# Robonaut.net
KiCad netlist of a schematic drawn in Altium Designer
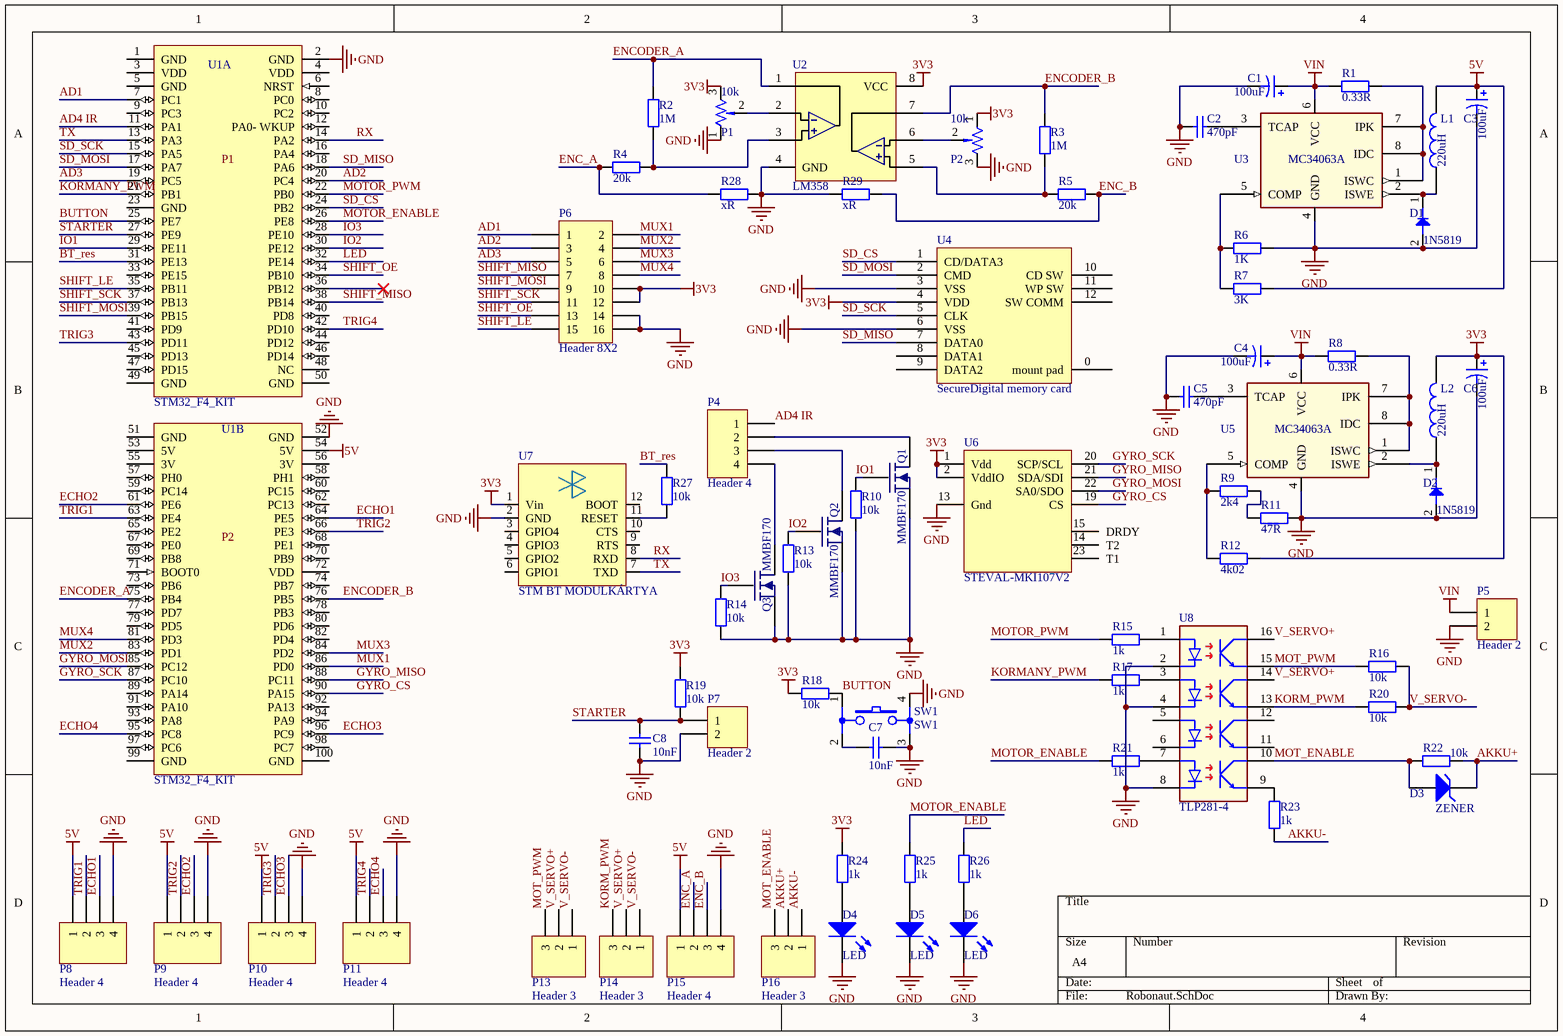
[diagram p0: Robonaut.SchDoc]

(export (version "E")
  (design (tool "Eeschema 10.0.6"))
  (components
    (comp (ref "C1")
      (value "100uF")
      (footprint "FP_CAP_ELKO_6,3X6,3")
      (description "Polarized Capacitor")
      (libsource (lib "Capacitor") (part "CAP_ELECT"))
    )
    (comp (ref "C2")
      (value "470pF")
      (footprint "FP_0805_CAP_085")
      (description "Capacitor")
      (libsource (lib "Capacitor") (part "CAP"))
    )
    (comp (ref "C3")
      (value "100uF")
      (footprint "FP_CAP_ELKO_6,3X6,3")
      (description "Polarized Capacitor")
      (libsource (lib "Capacitor") (part "CAP_ELECT"))
    )
    (comp (ref "C4")
      (value "100uF")
      (footprint "FP_CAP_ELKO_6,3X6,3")
      (description "Polarized Capacitor")
      (libsource (lib "Capacitor") (part "CAP_ELECT"))
    )
    (comp (ref "C5")
      (value "470pF")
      (footprint "FP_0805_CAP_085")
      (description "Capacitor")
      (libsource (lib "Capacitor") (part "CAP"))
    )
    (comp (ref "C6")
      (value "100uF")
      (footprint "FP_CAP_ELKO_6,3X6,3")
      (description "Polarized Capacitor")
      (libsource (lib "Capacitor") (part "CAP_ELECT"))
    )
    (comp (ref "C7")
      (value "10nF")
      (footprint "FP_0805_CAP_085")
      (description "Capacitor")
      (libsource (lib "Capacitor") (part "CAP"))
    )
    (comp (ref "C8")
      (value "10nF")
      (footprint "FP_0805_CAP_085")
      (description "Capacitor")
      (libsource (lib "Capacitor") (part "CAP"))
    )
    (comp (ref "D1") (value "1N5819") (footprint "FP_SOD-123") (libsource (lib "Diode") (part "DIODE")))
    (comp (ref "D2") (value "1N5819") (footprint "FP_SOD-123") (libsource (lib "Diode") (part "DIODE")))
    (comp (ref "D3")
      (value "ZENER")
      (footprint "FP_SOD-123")
      (description "Zener Diode")
      (libsource (lib "Diode") (part "ZENER"))
    )
    (comp (ref "D4")
      (value "LED")
      (footprint "FP_0805_LED_RED")
      (description "Typical RED GaAs LED")
      (libsource (lib "Led_optical") (part "LED"))
    )
    (comp (ref "D5")
      (value "LED")
      (footprint "FP_0805_LED_RED")
      (description "Typical RED GaAs LED")
      (libsource (lib "Led_optical") (part "LED"))
    )
    (comp (ref "D6")
      (value "LED")
      (footprint "FP_0805_LED_RED")
      (description "Typical RED GaAs LED")
      (libsource (lib "Led_optical") (part "LED"))
    )
    (comp (ref "L1")
      (value "220uH")
      (footprint "FP_IND_MURATA3131")
      (description "Inductor")
      (libsource (lib "Inductor") (part "IND"))
    )
    (comp (ref "L2")
      (value "220uH")
      (footprint "FP_IND_MURATA3131")
      (description "Inductor")
      (libsource (lib "Inductor") (part "IND"))
    )
    (comp (ref "P1") (value "10k") (footprint "Res Trimmer TH") (libsource (lib "Resistor") (part "POTI")))
    (comp (ref "P2") (value "10k") (footprint "Res Trimmer TH") (libsource (lib "Resistor") (part "POTI")))
    (comp (ref "P4")
      (value "Header 4")
      (footprint "HDR1X4")
      (description "Header, 4-Pin")
      (fields (field (name "PUBLISHER") "Altium Limited"))
      (libsource (lib "") (part "Header 4_1"))
    )
    (comp (ref "P5")
      (value "Header 2")
      (footprint "HDR1X2")
      (description "Header, 2-Pin")
      (fields (field (name "PUBLISHER") "Altium Limited"))
      (libsource (lib "Miscellaneous Connectors") (part "Header 2"))
    )
    (comp (ref "P6")
      (value "Header 8X2")
      (footprint "HDR2X8")
      (description "Header, 8-Pin, Dual row")
      (fields (field (name "PUBLISHER") "Altium Limited"))
      (libsource (lib "Miscellaneous Connectors") (part "Header 8X2"))
    )
    (comp (ref "P7")
      (value "Header 2")
      (footprint "HDR1X2")
      (description "Header, 2-Pin")
      (fields (field (name "PUBLISHER") "Altium Limited"))
      (libsource (lib "Miscellaneous Connectors") (part "Header 2"))
    )
    (comp (ref "P8")
      (value "Header 4")
      (footprint "HDR1X4")
      (description "Header, 4-Pin")
      (fields (field (name "PUBLISHER") "Altium Limited"))
      (libsource (lib "Miscellaneous Connectors") (part "Header 4"))
    )
    (comp (ref "P9")
      (value "Header 4")
      (footprint "HDR1X4")
      (description "Header, 4-Pin")
      (fields (field (name "PUBLISHER") "Altium Limited"))
      (libsource (lib "Miscellaneous Connectors") (part "Header 4"))
    )
    (comp (ref "P10")
      (value "Header 4")
      (footprint "HDR1X4")
      (description "Header, 4-Pin")
      (fields (field (name "PUBLISHER") "Altium Limited"))
      (libsource (lib "Miscellaneous Connectors") (part "Header 4"))
    )
    (comp (ref "P11")
      (value "Header 4")
      (footprint "HDR1X4")
      (description "Header, 4-Pin")
      (fields (field (name "PUBLISHER") "Altium Limited"))
      (libsource (lib "Miscellaneous Connectors") (part "Header 4"))
    )
    (comp (ref "P13")
      (value "Header 3")
      (footprint "HDR1X3")
      (description "Header, 3-Pin")
      (fields (field (name "PUBLISHER") "Altium Limited"))
      (libsource (lib "Miscellaneous Connectors") (part "Header 3"))
    )
    (comp (ref "P14")
      (value "Header 3")
      (footprint "HDR1X3")
      (description "Header, 3-Pin")
      (fields (field (name "PUBLISHER") "Altium Limited"))
      (libsource (lib "Miscellaneous Connectors") (part "Header 3"))
    )
    (comp (ref "P15")
      (value "Header 4")
      (footprint "HDR1X4")
      (description "Header, 4-Pin")
      (fields (field (name "PUBLISHER") "Altium Limited"))
      (libsource (lib "Miscellaneous Connectors") (part "Header 4"))
    )
    (comp (ref "P16")
      (value "Header 3")
      (footprint "HDR1X3")
      (description "Header, 3-Pin")
      (fields (field (name "PUBLISHER") "Altium Limited"))
      (libsource (lib "Miscellaneous Connectors") (part "Header 3"))
    )
    (comp (ref "Q1")
      (value "MMBF170")
      (footprint "BBMF170")
      (description "N fet  60V 500mA")
      (libsource (lib "FET") (part "MMBF170"))
    )
    (comp (ref "Q2")
      (value "MMBF170")
      (footprint "BBMF170")
      (description "N fet  60V 500mA")
      (libsource (lib "FET") (part "MMBF170"))
    )
    (comp (ref "Q3")
      (value "MMBF170")
      (footprint "BBMF170")
      (description "N fet  60V 500mA")
      (libsource (lib "FET") (part "MMBF170"))
    )
    (comp (ref "R1")
      (value "0.33R")
      (footprint "FP_0805_RES")
      (description "Resistor")
      (libsource (lib "Resistor") (part "RES"))
    )
    (comp (ref "R2")
      (value "1M")
      (footprint "FP_0805_RES")
      (description "Resistor")
      (libsource (lib "") (part "RES_1"))
    )
    (comp (ref "R3")
      (value "1M")
      (footprint "FP_0805_RES")
      (description "Resistor")
      (libsource (lib "") (part "RES_1"))
    )
    (comp (ref "R4")
      (value "20k")
      (footprint "FP_0805_RES")
      (description "Resistor")
      (libsource (lib "Resistor") (part "RES"))
    )
    (comp (ref "R5")
      (value "20k")
      (footprint "FP_0805_RES")
      (description "Resistor")
      (libsource (lib "Resistor") (part "RES"))
    )
    (comp (ref "R6")
      (value "1K")
      (footprint "FP_0805_RES")
      (description "Resistor")
      (libsource (lib "Resistor") (part "RES"))
    )
    (comp (ref "R7")
      (value "3K")
      (footprint "FP_0805_RES")
      (description "Resistor")
      (libsource (lib "Resistor") (part "RES"))
    )
    (comp (ref "R8")
      (value "0.33R")
      (footprint "FP_0805_RES")
      (description "Resistor")
      (libsource (lib "Resistor") (part "RES"))
    )
    (comp (ref "R9")
      (value "2k4")
      (footprint "FP_0805_RES")
      (description "Resistor")
      (libsource (lib "Resistor") (part "RES"))
    )
    (comp (ref "R10")
      (value "10k")
      (footprint "FP_0805_RES")
      (description "Resistor")
      (libsource (lib "") (part "RES_1"))
    )
    (comp (ref "R11")
      (value "47R")
      (footprint "FP_0805_RES")
      (description "Resistor")
      (libsource (lib "Resistor") (part "RES"))
    )
    (comp (ref "R12")
      (value "4k02")
      (footprint "FP_0805_RES")
      (description "Resistor")
      (libsource (lib "Resistor") (part "RES"))
    )
    (comp (ref "R13")
      (value "10k")
      (footprint "FP_0805_RES")
      (description "Resistor")
      (libsource (lib "") (part "RES_1"))
    )
    (comp (ref "R14")
      (value "10k")
      (footprint "FP_0805_RES")
      (description "Resistor")
      (libsource (lib "") (part "RES_1"))
    )
    (comp (ref "R15")
      (value "1k")
      (footprint "FP_0805_RES")
      (description "Resistor")
      (libsource (lib "Resistor") (part "RES"))
    )
    (comp (ref "R16")
      (value "10k")
      (footprint "FP_0805_RES")
      (description "Resistor")
      (libsource (lib "Resistor") (part "RES"))
    )
    (comp (ref "R17")
      (value "1k")
      (footprint "FP_0805_RES")
      (description "Resistor")
      (libsource (lib "Resistor") (part "RES"))
    )
    (comp (ref "R18")
      (value "10k")
      (footprint "FP_0805_RES")
      (description "Resistor")
      (libsource (lib "Resistor") (part "RES"))
    )
    (comp (ref "R19")
      (value "10k")
      (footprint "FP_0805_RES")
      (description "Resistor")
      (libsource (lib "") (part "RES_1"))
    )
    (comp (ref "R20")
      (value "10k")
      (footprint "FP_0805_RES")
      (description "Resistor")
      (libsource (lib "Resistor") (part "RES"))
    )
    (comp (ref "R21")
      (value "1k")
      (footprint "FP_0805_RES")
      (description "Resistor")
      (libsource (lib "Resistor") (part "RES"))
    )
    (comp (ref "R22")
      (value "10k")
      (footprint "FP_0805_RES")
      (description "Resistor")
      (libsource (lib "Resistor") (part "RES"))
    )
    (comp (ref "R23")
      (value "1k")
      (footprint "FP_0805_RES")
      (description "Resistor")
      (libsource (lib "") (part "RES_1"))
    )
    (comp (ref "R24")
      (value "1k")
      (footprint "FP_0805_RES")
      (description "Resistor")
      (libsource (lib "") (part "RES_1"))
    )
    (comp (ref "R25")
      (value "1k")
      (footprint "FP_0805_RES")
      (description "Resistor")
      (libsource (lib "") (part "RES_1"))
    )
    (comp (ref "R26")
      (value "1k")
      (footprint "FP_0805_RES")
      (description "Resistor")
      (libsource (lib "") (part "RES_1"))
    )
    (comp (ref "R27")
      (value "10k")
      (footprint "FP_0805_RES")
      (description "Resistor")
      (libsource (lib "") (part "RES_1"))
    )
    (comp (ref "R28")
      (value "xR")
      (footprint "FP_0805_RES")
      (description "Resistor")
      (libsource (lib "Resistor") (part "RES"))
    )
    (comp (ref "R29")
      (value "xR")
      (footprint "FP_0805_RES")
      (description "Resistor")
      (libsource (lib "Resistor") (part "RES"))
    )
    (comp (ref "SW1") (value "SW1") (footprint "FP_TACTBTN") (libsource (lib "Switch") (part "SW1")))
    (comp (ref "U1")
      (value "STM32_F4_KIT")
      (footprint "FP_STM32F4DISC")
      (description "STM32 F4 Discovery Evaluation Kit")
      (libsource (lib "Modul") (part "STM32F4DISCOVERY"))
    )
    (comp (ref "U2")
      (value "LM358")
      (footprint "FP_SO8_MS012AA")
      (description "Low power dual operational amplifiers")
      (libsource (lib "Analog") (part "LM358"))
    )
    (comp (ref "U3")
      (value "MC34063A")
      (footprint "FP_SO8_MS012AA")
      (libsource (lib "Supply") (part "MC34063A"))
    )
    (comp (ref "U4")
      (value "SecureDigital memory card")
      (footprint "FP_CONN_SD")
      (libsource (lib "Connector") (part "SD card"))
    )
    (comp (ref "U5")
      (value "MC34063A")
      (footprint "FP_SO8_MS012AA")
      (libsource (lib "Supply") (part "MC34063A"))
    )
    (comp (ref "U6")
      (value "STEVAL-MKI107V2")
      (footprint "STEVAL-MKI107V2 DIL24 Adapter")
      (description "Three-axis digital output gyroscope")
      (fields (field (name "MANUFACTURER") "STMicroelectronic"))
      (libsource (lib "Modul") (part "STEVAL-MKI107V2"))
    )
    (comp (ref "U7")
      (value "STM BT MODULKÁRTYA")
      (footprint "STM BT MODUL")
      (description "bluetooth modulkártya")
      (libsource (lib "Modul") (part "STM BT MODULKÁRTYA"))
    )
    (comp (ref "U8")
      (value "TLP281-4")
      (footprint "TLP281-4")
      (description "Optocsatoló 4X")
      (libsource (lib "Led_optical") (part "TLP281-4"))
    )
  )
  (nets
    (net (code "1") (name "/AD1") (class "Default")
      (node (ref "P6") (pin "1") (pinfunction "1_1") (pintype "passive"))
      (node (ref "U1") (pin "7") (pinfunction "PC1_7") (pintype "bidirectional"))
    )
    (net (code "2") (name "/AD2") (class "Default")
      (node (ref "P6") (pin "3") (pinfunction "3_3") (pintype "passive"))
      (node (ref "U1") (pin "20") (pinfunction "PC4_20") (pintype "bidirectional"))
    )
    (net (code "3") (name "/AD3") (class "Default")
      (node (ref "P6") (pin "5") (pinfunction "5_5") (pintype "passive"))
      (node (ref "U1") (pin "19") (pinfunction "PC5_19") (pintype "bidirectional"))
    )
    (net (code "4") (name "/AD4 IR") (class "Default")
      (node (ref "P4") (pin "1") (pinfunction "1_1") (pintype "passive"))
      (node (ref "U1") (pin "11") (pinfunction "PA1_11") (pintype "bidirectional"))
    )
    (net (code "5") (name "/AKKU+") (class "Default")
      (node (ref "D3") (pin "2") (pinfunction "K_2") (pintype "passive"))
      (node (ref "P16") (pin "2") (pinfunction "2_2") (pintype "passive"))
      (node (ref "R22") (pin "2") (pinfunction "2_2") (pintype "passive"))
    )
    (net (code "6") (name "/AKKU-") (class "Default")
      (node (ref "P16") (pin "1") (pinfunction "1_1") (pintype "passive"))
      (node (ref "R23") (pin "1") (pinfunction "1_1") (pintype "passive"))
    )
    (net (code "7") (name "/BT_res") (class "Default")
      (node (ref "R27") (pin "2") (pinfunction "2_2") (pintype "passive"))
      (node (ref "U1") (pin "31") (pinfunction "PE13_31") (pintype "bidirectional"))
    )
    (net (code "8") (name "/BUTTON") (class "Default")
      (node (ref "R18") (pin "2") (pinfunction "2_2") (pintype "passive"))
      (node (ref "SW1") (pin "1") (pinfunction "1_1") (pintype "passive"))
      (node (ref "U1") (pin "25") (pinfunction "PE7_25") (pintype "bidirectional"))
    )
    (net (code "9") (name "/ECHO1") (class "Default")
      (node (ref "P8") (pin "3") (pinfunction "3_3") (pintype "passive"))
      (node (ref "U1") (pin "64") (pinfunction "PE5_64") (pintype "bidirectional"))
    )
    (net (code "10") (name "/ECHO2") (class "Default")
      (node (ref "P9") (pin "3") (pinfunction "3_3") (pintype "passive"))
      (node (ref "U1") (pin "61") (pinfunction "PE6_61") (pintype "bidirectional"))
    )
    (net (code "11") (name "/ECHO3") (class "Default")
      (node (ref "P10") (pin "3") (pinfunction "3_3") (pintype "passive"))
      (node (ref "U1") (pin "96") (pinfunction "PC9_96") (pintype "bidirectional"))
    )
    (net (code "12") (name "/ECHO4") (class "Default")
      (node (ref "P11") (pin "3") (pinfunction "3_3") (pintype "passive"))
      (node (ref "U1") (pin "95") (pinfunction "PC8_95") (pintype "bidirectional"))
    )
    (net (code "13") (name "/ENCODER_A") (class "Default")
      (node (ref "R2") (pin "2") (pinfunction "2_2") (pintype "passive"))
      (node (ref "U1") (pin "75") (pinfunction "PB4_75") (pintype "bidirectional"))
      (node (ref "U2") (pin "1") (pintype "passive"))
    )
    (net (code "14") (name "/ENCODER_B") (class "Default")
      (node (ref "R3") (pin "2") (pinfunction "2_2") (pintype "passive"))
      (node (ref "U1") (pin "76") (pinfunction "PB5_76") (pintype "bidirectional"))
      (node (ref "U2") (pin "7") (pintype "passive"))
    )
    (net (code "15") (name "/ENC_A") (class "Default")
      (node (ref "P15") (pin "2") (pinfunction "2_2") (pintype "passive"))
      (node (ref "R28") (pin "1") (pinfunction "1_1") (pintype "passive"))
      (node (ref "R4") (pin "1") (pinfunction "1_1") (pintype "passive"))
    )
    (net (code "16") (name "/ENC_B") (class "Default")
      (node (ref "P15") (pin "3") (pinfunction "3_3") (pintype "passive"))
      (node (ref "R29") (pin "2") (pinfunction "2_2") (pintype "passive"))
      (node (ref "R5") (pin "2") (pinfunction "2_2") (pintype "passive"))
    )
    (net (code "17") (name "/GYRO_CS") (class "Default")
      (node (ref "U1") (pin "90") (pinfunction "PA15_90") (pintype "bidirectional"))
      (node (ref "U6") (pin "19") (pinfunction "CS_19") (pintype "passive"))
    )
    (net (code "18") (name "/GYRO_MISO") (class "Default")
      (node (ref "U1") (pin "88") (pinfunction "PC11_88") (pintype "bidirectional"))
      (node (ref "U6") (pin "21") (pinfunction "SDA/SDI_21") (pintype "passive"))
    )
    (net (code "19") (name "/GYRO_MOSI") (class "Default")
      (node (ref "U1") (pin "85") (pinfunction "PC12_85") (pintype "bidirectional"))
      (node (ref "U6") (pin "22") (pinfunction "SA0/SDO_22") (pintype "passive"))
    )
    (net (code "20") (name "/GYRO_SCK") (class "Default")
      (node (ref "U1") (pin "87") (pinfunction "PC10_87") (pintype "bidirectional"))
      (node (ref "U6") (pin "20") (pinfunction "SCP/SCL_20") (pintype "passive"))
    )
    (net (code "21") (name "/IO1") (class "Default")
      (node (ref "Q1") (pin "G") (pinfunction "G_G") (pintype "passive"))
      (node (ref "R10") (pin "2") (pinfunction "2_2") (pintype "passive"))
      (node (ref "U1") (pin "29") (pinfunction "PE11_29") (pintype "bidirectional"))
    )
    (net (code "22") (name "/IO2") (class "Default")
      (node (ref "Q2") (pin "G") (pinfunction "G_G") (pintype "passive"))
      (node (ref "R13") (pin "2") (pinfunction "2_2") (pintype "passive"))
      (node (ref "U1") (pin "30") (pinfunction "PE12_30") (pintype "bidirectional"))
    )
    (net (code "23") (name "/IO3") (class "Default")
      (node (ref "Q3") (pin "G") (pinfunction "G_G") (pintype "passive"))
      (node (ref "R14") (pin "2") (pinfunction "2_2") (pintype "passive"))
      (node (ref "U1") (pin "28") (pinfunction "PE10_28") (pintype "bidirectional"))
    )
    (net (code "24") (name "/KORMANY_PWM") (class "Default")
      (node (ref "R17") (pin "1") (pinfunction "1_1") (pintype "passive"))
      (node (ref "U1") (pin "21") (pinfunction "PB1_21") (pintype "bidirectional"))
    )
    (net (code "25") (name "/KORM_PWM") (class "Default")
      (node (ref "P14") (pin "3") (pinfunction "3_3") (pintype "passive"))
      (node (ref "R20") (pin "1") (pinfunction "1_1") (pintype "passive"))
      (node (ref "U8") (pin "13") (pintype "passive"))
    )
    (net (code "26") (name "/LED") (class "Default")
      (node (ref "R26") (pin "2") (pinfunction "2_2") (pintype "passive"))
      (node (ref "U1") (pin "32") (pinfunction "PE14_32") (pintype "bidirectional"))
    )
    (net (code "27") (name "/MOTOR_ENABLE") (class "Default")
      (node (ref "R21") (pin "1") (pinfunction "1_1") (pintype "passive"))
      (node (ref "R25") (pin "2") (pinfunction "2_2") (pintype "passive"))
      (node (ref "U1") (pin "26") (pinfunction "PE8_26") (pintype "bidirectional"))
    )
    (net (code "28") (name "/MOTOR_PWM") (class "Default")
      (node (ref "R15") (pin "1") (pinfunction "1_1") (pintype "passive"))
      (node (ref "U1") (pin "22") (pinfunction "PB0_22") (pintype "bidirectional"))
    )
    (net (code "29") (name "/MOT_ENABLE") (class "Default")
      (node (ref "D3") (pin "1") (pinfunction "A_1") (pintype "passive"))
      (node (ref "P16") (pin "3") (pinfunction "3_3") (pintype "passive"))
      (node (ref "R22") (pin "1") (pinfunction "1_1") (pintype "passive"))
      (node (ref "U8") (pin "10") (pintype "passive"))
    )
    (net (code "30") (name "/MOT_PWM") (class "Default")
      (node (ref "P13") (pin "3") (pinfunction "3_3") (pintype "passive"))
      (node (ref "R16") (pin "1") (pinfunction "1_1") (pintype "passive"))
      (node (ref "U8") (pin "15") (pintype "passive"))
    )
    (net (code "31") (name "/MUX1") (class "Default")
      (node (ref "P6") (pin "2") (pinfunction "2_2") (pintype "passive"))
      (node (ref "U1") (pin "86") (pinfunction "PD0_86") (pintype "bidirectional"))
    )
    (net (code "32") (name "/MUX2") (class "Default")
      (node (ref "P6") (pin "4") (pinfunction "4_4") (pintype "passive"))
      (node (ref "U1") (pin "83") (pinfunction "PD1_83") (pintype "bidirectional"))
    )
    (net (code "33") (name "/MUX3") (class "Default")
      (node (ref "P6") (pin "6") (pinfunction "6_6") (pintype "passive"))
      (node (ref "U1") (pin "84") (pinfunction "PD2_84") (pintype "bidirectional"))
    )
    (net (code "34") (name "/MUX4") (class "Default")
      (node (ref "P6") (pin "8") (pinfunction "8_8") (pintype "passive"))
      (node (ref "U1") (pin "81") (pinfunction "PD3_81") (pintype "bidirectional"))
    )
    (net (code "35") (name "/RX") (class "Default")
      (node (ref "U1") (pin "14") (pinfunction "PA2_14") (pintype "bidirectional"))
      (node (ref "U7") (pin "8") (pinfunction "RXD_8") (pintype "passive"))
    )
    (net (code "36") (name "/SD_CS") (class "Default")
      (node (ref "U1") (pin "24") (pinfunction "PB2_24") (pintype "bidirectional"))
      (node (ref "U4") (pin "1") (pinfunction "CD/DATA3_1") (pintype "passive"))
    )
    (net (code "37") (name "/SD_MISO") (class "Default")
      (node (ref "U1") (pin "18") (pinfunction "PA6_18") (pintype "bidirectional"))
      (node (ref "U4") (pin "7") (pinfunction "DATA0_7") (pintype "passive"))
    )
    (net (code "38") (name "/SD_MOSI") (class "Default")
      (node (ref "U1") (pin "17") (pinfunction "PA7_17") (pintype "bidirectional"))
      (node (ref "U4") (pin "2") (pinfunction "CMD_2") (pintype "passive"))
    )
    (net (code "39") (name "/SD_SCK") (class "Default")
      (node (ref "U1") (pin "15") (pinfunction "PA5_15") (pintype "bidirectional"))
      (node (ref "U4") (pin "5") (pinfunction "CLK_5") (pintype "passive"))
    )
    (net (code "40") (name "/SHIFT_LE") (class "Default")
      (node (ref "P6") (pin "15") (pinfunction "15_15") (pintype "passive"))
      (node (ref "U1") (pin "35") (pinfunction "PB11_35") (pintype "bidirectional"))
    )
    (net (code "41") (name "/SHIFT_MISO") (class "Default")
      (node (ref "P6") (pin "7") (pinfunction "7_7") (pintype "passive"))
      (node (ref "U1") (pin "38") (pinfunction "PB14_38") (pintype "bidirectional"))
    )
    (net (code "42") (name "/SHIFT_MOSI") (class "Default")
      (node (ref "P6") (pin "9") (pinfunction "9_9") (pintype "passive"))
      (node (ref "U1") (pin "39") (pinfunction "PB15_39") (pintype "bidirectional"))
    )
    (net (code "43") (name "/SHIFT_OE") (class "Default")
      (node (ref "P6") (pin "13") (pinfunction "13_13") (pintype "passive"))
      (node (ref "U1") (pin "34") (pinfunction "PB10_34") (pintype "bidirectional"))
    )
    (net (code "44") (name "/SHIFT_SCK") (class "Default")
      (node (ref "P6") (pin "11") (pinfunction "11_11") (pintype "passive"))
      (node (ref "U1") (pin "37") (pinfunction "PB13_37") (pintype "bidirectional"))
    )
    (net (code "45") (name "/STARTER") (class "Default")
      (node (ref "C8") (pin "2") (pinfunction "2_2") (pintype "passive"))
      (node (ref "P7") (pin "1") (pinfunction "1_1") (pintype "passive"))
      (node (ref "R19") (pin "1") (pinfunction "1_1") (pintype "passive"))
      (node (ref "U1") (pin "27") (pinfunction "PE9_27") (pintype "bidirectional"))
    )
    (net (code "46") (name "/TRIG1") (class "Default")
      (node (ref "P8") (pin "2") (pinfunction "2_2") (pintype "passive"))
      (node (ref "U1") (pin "63") (pinfunction "PE4_63") (pintype "bidirectional"))
    )
    (net (code "47") (name "/TRIG2") (class "Default")
      (node (ref "P9") (pin "2") (pinfunction "2_2") (pintype "passive"))
      (node (ref "U1") (pin "66") (pinfunction "PE3_66") (pintype "bidirectional"))
    )
    (net (code "48") (name "/TRIG3") (class "Default")
      (node (ref "P10") (pin "2") (pinfunction "2_2") (pintype "passive"))
      (node (ref "U1") (pin "43") (pinfunction "PD11_43") (pintype "bidirectional"))
    )
    (net (code "49") (name "/TRIG4") (class "Default")
      (node (ref "P11") (pin "2") (pinfunction "2_2") (pintype "passive"))
      (node (ref "U1") (pin "42") (pinfunction "PD10_42") (pintype "bidirectional"))
    )
    (net (code "50") (name "/TX") (class "Default")
      (node (ref "U1") (pin "13") (pinfunction "PA3_13") (pintype "bidirectional"))
      (node (ref "U7") (pin "7") (pinfunction "TXD_7") (pintype "passive"))
    )
    (net (code "51") (name "/V_SERVO+") (class "Default")
      (node (ref "P13") (pin "2") (pinfunction "2_2") (pintype "passive"))
      (node (ref "P14") (pin "2") (pinfunction "2_2") (pintype "passive"))
      (node (ref "U8") (pin "14") (pintype "passive"))
      (node (ref "U8") (pin "16") (pintype "passive"))
    )
    (net (code "52") (name "/V_SERVO-") (class "Default")
      (node (ref "P13") (pin "1") (pinfunction "1_1") (pintype "passive"))
      (node (ref "P14") (pin "1") (pinfunction "1_1") (pintype "passive"))
      (node (ref "R16") (pin "2") (pinfunction "2_2") (pintype "passive"))
      (node (ref "R20") (pin "2") (pinfunction "2_2") (pintype "passive"))
    )
    (net (code "53") (name "3V3") (class "Default")
      (node (ref "C6") (pin "P") (pinfunction "P_P") (pintype "passive"))
      (node (ref "L2") (pin "2") (pinfunction "2_2") (pintype "passive"))
      (node (ref "P1") (pin "3") (pinfunction "2_3") (pintype "passive"))
      (node (ref "P2") (pin "1") (pinfunction "1_1") (pintype "passive"))
      (node (ref "P6") (pin "10") (pinfunction "10_10") (pintype "passive"))
      (node (ref "P6") (pin "12") (pinfunction "12_12") (pintype "passive"))
      (node (ref "R12") (pin "2") (pinfunction "2_2") (pintype "passive"))
      (node (ref "R18") (pin "1") (pinfunction "1_1") (pintype "passive"))
      (node (ref "R19") (pin "2") (pinfunction "2_2") (pintype "passive"))
      (node (ref "R24") (pin "2") (pinfunction "2_2") (pintype "passive"))
      (node (ref "U2") (pin "8") (pinfunction "VCC_8") (pintype "passive"))
      (node (ref "U4") (pin "4") (pinfunction "VDD_4") (pintype "passive"))
      (node (ref "U6") (pin "1") (pinfunction "Vdd_1") (pintype "power_in"))
      (node (ref "U6") (pin "2") (pinfunction "VddIO_2") (pintype "power_in"))
      (node (ref "U7") (pin "1") (pinfunction "Vin_1") (pintype "passive"))
    )
    (net (code "54") (name "5V") (class "Default")
      (node (ref "C3") (pin "P") (pinfunction "P_P") (pintype "passive"))
      (node (ref "L1") (pin "2") (pinfunction "2_2") (pintype "passive"))
      (node (ref "P10") (pin "1") (pinfunction "1_1") (pintype "passive"))
      (node (ref "P11") (pin "1") (pinfunction "1_1") (pintype "passive"))
      (node (ref "P15") (pin "1") (pinfunction "1_1") (pintype "passive"))
      (node (ref "P8") (pin "1") (pinfunction "1_1") (pintype "passive"))
      (node (ref "P9") (pin "1") (pinfunction "1_1") (pintype "passive"))
      (node (ref "R7") (pin "2") (pinfunction "2_2") (pintype "passive"))
      (node (ref "U1") (pin "54") (pinfunction "5V_54") (pintype "power_in"))
    )
    (net (code "55") (name "GND") (class "Default")
      (node (ref "C1") (pin "N") (pinfunction "N_N") (pintype "passive"))
      (node (ref "C2") (pin "1") (pinfunction "1_1") (pintype "passive"))
      (node (ref "C3") (pin "N") (pinfunction "N_N") (pintype "passive"))
      (node (ref "C4") (pin "N") (pinfunction "N_N") (pintype "passive"))
      (node (ref "C5") (pin "1") (pinfunction "1_1") (pintype "passive"))
      (node (ref "C6") (pin "N") (pinfunction "N_N") (pintype "passive"))
      (node (ref "C7") (pin "2") (pinfunction "2_2") (pintype "passive"))
      (node (ref "C8") (pin "1") (pinfunction "1_1") (pintype "passive"))
      (node (ref "D1") (pin "2") (pinfunction "2_2") (pintype "passive"))
      (node (ref "D2") (pin "2") (pinfunction "2_2") (pintype "passive"))
      (node (ref "D4") (pin "2") (pinfunction "K_2") (pintype "passive"))
      (node (ref "D5") (pin "2") (pinfunction "K_2") (pintype "passive"))
      (node (ref "D6") (pin "2") (pinfunction "K_2") (pintype "passive"))
      (node (ref "P1") (pin "1") (pinfunction "1_1") (pintype "passive"))
      (node (ref "P10") (pin "4") (pinfunction "4_4") (pintype "passive"))
      (node (ref "P11") (pin "4") (pinfunction "4_4") (pintype "passive"))
      (node (ref "P15") (pin "4") (pinfunction "4_4") (pintype "passive"))
      (node (ref "P2") (pin "3") (pinfunction "2_3") (pintype "passive"))
      (node (ref "P5") (pin "2") (pinfunction "2_2") (pintype "passive"))
      (node (ref "P6") (pin "14") (pinfunction "14_14") (pintype "passive"))
      (node (ref "P6") (pin "16") (pinfunction "16_16") (pintype "passive"))
      (node (ref "P7") (pin "2") (pinfunction "2_2") (pintype "passive"))
      (node (ref "P8") (pin "4") (pinfunction "4_4") (pintype "passive"))
      (node (ref "P9") (pin "4") (pinfunction "4_4") (pintype "passive"))
      (node (ref "Q1") (pin "S") (pinfunction "S_S") (pintype "passive"))
      (node (ref "Q2") (pin "S") (pinfunction "S_S") (pintype "passive"))
      (node (ref "Q3") (pin "S") (pinfunction "S_S") (pintype "passive"))
      (node (ref "R10") (pin "1") (pinfunction "1_1") (pintype "passive"))
      (node (ref "R11") (pin "2") (pinfunction "2_2") (pintype "passive"))
      (node (ref "R13") (pin "1") (pinfunction "1_1") (pintype "passive"))
      (node (ref "R14") (pin "1") (pinfunction "1_1") (pintype "passive"))
      (node (ref "R28") (pin "2") (pinfunction "2_2") (pintype "passive"))
      (node (ref "R29") (pin "1") (pinfunction "1_1") (pintype "passive"))
      (node (ref "R6") (pin "2") (pinfunction "2_2") (pintype "passive"))
      (node (ref "SW1") (pin "3") (pinfunction "3_3") (pintype "passive"))
      (node (ref "SW1") (pin "4") (pinfunction "4_4") (pintype "passive"))
      (node (ref "U1") (pin "2") (pinfunction "GND_2") (pintype "power_in"))
      (node (ref "U1") (pin "52") (pinfunction "GND_52") (pintype "power_in"))
      (node (ref "U2") (pin "4") (pinfunction "GND_4") (pintype "passive"))
      (node (ref "U3") (pin "4") (pinfunction "GND_4") (pintype "passive"))
      (node (ref "U4") (pin "3") (pinfunction "VSS_3") (pintype "passive"))
      (node (ref "U4") (pin "6") (pinfunction "VSS_6") (pintype "passive"))
      (node (ref "U5") (pin "4") (pinfunction "GND_4") (pintype "passive"))
      (node (ref "U6") (pin "13") (pinfunction "Gnd_13") (pintype "power_in"))
      (node (ref "U7") (pin "2") (pinfunction "GND_2") (pintype "passive"))
      (node (ref "U8") (pin "2") (pintype "passive"))
      (node (ref "U8") (pin "4") (pintype "passive"))
      (node (ref "U8") (pin "8") (pintype "passive"))
    )
    (net (code "56") (name "Net-(C7-Pad1)") (class "Default")
      (node (ref "C7") (pin "1") (pinfunction "1_1") (pintype "passive"))
      (node (ref "SW1") (pin "2") (pinfunction "2_2") (pintype "passive"))
    )
    (net (code "57") (name "Net-(D4-A)") (class "Default")
      (node (ref "D4") (pin "1") (pinfunction "A_1") (pintype "passive"))
      (node (ref "R24") (pin "1") (pinfunction "1_1") (pintype "passive"))
    )
    (net (code "58") (name "Net-(D5-A)") (class "Default")
      (node (ref "D5") (pin "1") (pinfunction "A_1") (pintype "passive"))
      (node (ref "R25") (pin "1") (pinfunction "1_1") (pintype "passive"))
    )
    (net (code "59") (name "Net-(D6-A)") (class "Default")
      (node (ref "D6") (pin "1") (pinfunction "A_1") (pintype "passive"))
      (node (ref "R26") (pin "1") (pinfunction "1_1") (pintype "passive"))
    )
    (net (code "60") (name "Net-(P1-t)") (class "Default")
      (node (ref "P1") (pin "2") (pinfunction "t_2") (pintype "passive"))
      (node (ref "U2") (pin "2") (pintype "passive"))
    )
    (net (code "61") (name "Net-(P2-t)") (class "Default")
      (node (ref "P2") (pin "2") (pinfunction "t_2") (pintype "passive"))
      (node (ref "U2") (pin "6") (pintype "passive"))
    )
    (net (code "62") (name "Net-(P4-Pad2)") (class "Default")
      (node (ref "P4") (pin "2") (pinfunction "2_2") (pintype "passive"))
      (node (ref "Q1") (pin "D") (pinfunction "D_D") (pintype "passive"))
    )
    (net (code "63") (name "Net-(P4-Pad3)") (class "Default")
      (node (ref "P4") (pin "3") (pinfunction "3_3") (pintype "passive"))
      (node (ref "Q2") (pin "D") (pinfunction "D_D") (pintype "passive"))
    )
    (net (code "64") (name "Net-(P4-Pad4)") (class "Default")
      (node (ref "P4") (pin "4") (pinfunction "4_4") (pintype "passive"))
      (node (ref "Q3") (pin "D") (pinfunction "D_D") (pintype "passive"))
    )
    (net (code "65") (name "Net-(R2-Pad1)") (class "Default")
      (node (ref "R2") (pin "1") (pinfunction "1_1") (pintype "passive"))
      (node (ref "R4") (pin "2") (pinfunction "2_2") (pintype "passive"))
      (node (ref "U2") (pin "3") (pintype "passive"))
    )
    (net (code "66") (name "Net-(R3-Pad1)") (class "Default")
      (node (ref "R3") (pin "1") (pinfunction "1_1") (pintype "passive"))
      (node (ref "R5") (pin "1") (pinfunction "1_1") (pintype "passive"))
      (node (ref "U2") (pin "5") (pintype "passive"))
    )
    (net (code "67") (name "Net-(R11-Pad1)") (class "Default")
      (node (ref "R11") (pin "1") (pinfunction "1_1") (pintype "passive"))
      (node (ref "R9") (pin "2") (pinfunction "2_2") (pintype "passive"))
    )
    (net (code "68") (name "Net-(R15-Pad2)") (class "Default")
      (node (ref "R15") (pin "2") (pinfunction "2_2") (pintype "passive"))
      (node (ref "U8") (pin "1") (pintype "passive"))
    )
    (net (code "69") (name "Net-(R17-Pad2)") (class "Default")
      (node (ref "R17") (pin "2") (pinfunction "2_2") (pintype "passive"))
      (node (ref "U8") (pin "3") (pintype "passive"))
    )
    (net (code "70") (name "Net-(R21-Pad2)") (class "Default")
      (node (ref "R21") (pin "2") (pinfunction "2_2") (pintype "passive"))
      (node (ref "U8") (pin "7") (pintype "passive"))
    )
    (net (code "71") (name "Net-(R23-Pad2)") (class "Default")
      (node (ref "R23") (pin "2") (pinfunction "2_2") (pintype "passive"))
      (node (ref "U8") (pin "9") (pintype "passive"))
    )
    (net (code "72") (name "Net-(U3-COMP)") (class "Default")
      (node (ref "R6") (pin "1") (pinfunction "1_1") (pintype "passive"))
      (node (ref "R7") (pin "1") (pinfunction "1_1") (pintype "passive"))
      (node (ref "U3") (pin "5") (pinfunction "COMP_5") (pintype "input"))
    )
    (net (code "73") (name "Net-(U3-IDC)") (class "Default")
      (node (ref "R1") (pin "2") (pinfunction "2_2") (pintype "passive"))
      (node (ref "U3") (pin "1") (pinfunction "ISWC_1") (pintype "output"))
      (node (ref "U3") (pin "7") (pinfunction "IPK_7") (pintype "passive"))
      (node (ref "U3") (pin "8") (pinfunction "IDC_8") (pintype "passive"))
    )
    (net (code "74") (name "Net-(U3-ISWE)") (class "Default")
      (node (ref "D1") (pin "1") (pinfunction "1_1") (pintype "passive"))
      (node (ref "L1") (pin "1") (pinfunction "1_1") (pintype "passive"))
      (node (ref "U3") (pin "2") (pinfunction "ISWE_2") (pintype "output"))
    )
    (net (code "75") (name "Net-(U3-TCAP)") (class "Default")
      (node (ref "C2") (pin "2") (pinfunction "2_2") (pintype "passive"))
      (node (ref "U3") (pin "3") (pinfunction "TCAP_3") (pintype "passive"))
    )
    (net (code "76") (name "Net-(U5-COMP)") (class "Default")
      (node (ref "R12") (pin "1") (pinfunction "1_1") (pintype "passive"))
      (node (ref "R9") (pin "1") (pinfunction "1_1") (pintype "passive"))
      (node (ref "U5") (pin "5") (pinfunction "COMP_5") (pintype "input"))
    )
    (net (code "77") (name "Net-(U5-IDC)") (class "Default")
      (node (ref "R8") (pin "2") (pinfunction "2_2") (pintype "passive"))
      (node (ref "U5") (pin "1") (pinfunction "ISWC_1") (pintype "output"))
      (node (ref "U5") (pin "7") (pinfunction "IPK_7") (pintype "passive"))
      (node (ref "U5") (pin "8") (pinfunction "IDC_8") (pintype "passive"))
    )
    (net (code "78") (name "Net-(U5-ISWE)") (class "Default")
      (node (ref "D2") (pin "1") (pinfunction "1_1") (pintype "passive"))
      (node (ref "L2") (pin "1") (pinfunction "1_1") (pintype "passive"))
      (node (ref "U5") (pin "2") (pinfunction "ISWE_2") (pintype "output"))
    )
    (net (code "79") (name "Net-(U5-TCAP)") (class "Default")
      (node (ref "C5") (pin "2") (pinfunction "2_2") (pintype "passive"))
      (node (ref "U5") (pin "3") (pinfunction "TCAP_3") (pintype "passive"))
    )
    (net (code "80") (name "Net-(U7-RESET)") (class "Default")
      (node (ref "R27") (pin "1") (pinfunction "1_1") (pintype "passive"))
      (node (ref "U7") (pin "11") (pinfunction "RESET_11") (pintype "passive"))
    )
    (net (code "81") (name "VIN") (class "Default")
      (node (ref "C1") (pin "P") (pinfunction "P_P") (pintype "passive"))
      (node (ref "C4") (pin "P") (pinfunction "P_P") (pintype "passive"))
      (node (ref "P5") (pin "1") (pinfunction "1_1") (pintype "passive"))
      (node (ref "R1") (pin "1") (pinfunction "1_1") (pintype "passive"))
      (node (ref "R8") (pin "1") (pinfunction "1_1") (pintype "passive"))
      (node (ref "U3") (pin "6") (pinfunction "VCC_6") (pintype "passive"))
      (node (ref "U5") (pin "6") (pinfunction "VCC_6") (pintype "passive"))
    )
    (net (code "82") (name "unconnected-(U1A-GND-Pad1)") (class "Default")
      (node (ref "U1") (pin "1") (pinfunction "GND_1") (pintype "power_in"))
    )
    (net (code "83") (name "unconnected-(U1A-GND-Pad5)") (class "Default")
      (node (ref "U1") (pin "5") (pinfunction "GND_5") (pintype "power_in"))
    )
    (net (code "84") (name "unconnected-(U1A-GND-Pad23)") (class "Default")
      (node (ref "U1") (pin "23") (pinfunction "GND_23") (pintype "power_in"))
    )
    (net (code "85") (name "unconnected-(U1A-GND-Pad49)") (class "Default")
      (node (ref "U1") (pin "49") (pinfunction "GND_49") (pintype "power_in"))
    )
    (net (code "86") (name "unconnected-(U1A-GND-Pad50)") (class "Default")
      (node (ref "U1") (pin "50") (pinfunction "GND_50") (pintype "power_in"))
    )
    (net (code "87") (name "unconnected-(U1A-NC-Pad48)") (class "Default")
      (node (ref "U1") (pin "48") (pinfunction "NC_48") (pintype "passive"))
    )
    (net (code "88") (name "unconnected-(U1A-NRST-Pad6)") (class "Default")
      (node (ref "U1") (pin "6") (pinfunction "NRST_6") (pintype "input"))
    )
    (net (code "89") (name "unconnected-(U1A-PA0-_WKUP-Pad12)") (class "Default")
      (node (ref "U1") (pin "12") (pinfunction "PA0-_WKUP_12") (pintype "bidirectional"))
    )
    (net (code "90") (name "unconnected-(U1A-PA4-Pad16)") (class "Default")
      (node (ref "U1") (pin "16") (pinfunction "PA4_16") (pintype "bidirectional"))
    )
    (net (code "91") (name "unconnected-(U1A-PB12-Pad36)") (class "Default")
      (node (ref "U1") (pin "36") (pinfunction "PB12_36") (pintype "bidirectional+no_connect"))
    )
    (net (code "92") (name "unconnected-(U1A-PC0-Pad8)") (class "Default")
      (node (ref "U1") (pin "8") (pinfunction "PC0_8") (pintype "bidirectional"))
    )
    (net (code "93") (name "unconnected-(U1A-PC2-Pad10)") (class "Default")
      (node (ref "U1") (pin "10") (pinfunction "PC2_10") (pintype "bidirectional"))
    )
    (net (code "94") (name "unconnected-(U1A-PC3-Pad9)") (class "Default")
      (node (ref "U1") (pin "9") (pinfunction "PC3_9") (pintype "bidirectional"))
    )
    (net (code "95") (name "unconnected-(U1A-PD8-Pad40)") (class "Default")
      (node (ref "U1") (pin "40") (pinfunction "PD8_40") (pintype "bidirectional"))
    )
    (net (code "96") (name "unconnected-(U1A-PD9-Pad41)") (class "Default")
      (node (ref "U1") (pin "41") (pinfunction "PD9_41") (pintype "bidirectional"))
    )
    (net (code "97") (name "unconnected-(U1A-PD12-Pad44)") (class "Default")
      (node (ref "U1") (pin "44") (pinfunction "PD12_44") (pintype "bidirectional"))
    )
    (net (code "98") (name "unconnected-(U1A-PD13-Pad45)") (class "Default")
      (node (ref "U1") (pin "45") (pinfunction "PD13_45") (pintype "bidirectional"))
    )
    (net (code "99") (name "unconnected-(U1A-PD14-Pad46)") (class "Default")
      (node (ref "U1") (pin "46") (pinfunction "PD14_46") (pintype "bidirectional"))
    )
    (net (code "100") (name "unconnected-(U1A-PD15-Pad47)") (class "Default")
      (node (ref "U1") (pin "47") (pinfunction "PD15_47") (pintype "bidirectional"))
    )
    (net (code "101") (name "unconnected-(U1A-PE15-Pad33)") (class "Default")
      (node (ref "U1") (pin "33") (pinfunction "PE15_33") (pintype "bidirectional"))
    )
    (net (code "102") (name "unconnected-(U1A-VDD-Pad3)") (class "Default")
      (node (ref "U1") (pin "3") (pinfunction "VDD_3") (pintype "power_in"))
    )
    (net (code "103") (name "unconnected-(U1A-VDD-Pad4)") (class "Default")
      (node (ref "U1") (pin "4") (pinfunction "VDD_4") (pintype "power_in"))
    )
    (net (code "104") (name "unconnected-(U1B-3V-Pad55)") (class "Default")
      (node (ref "U1") (pin "55") (pinfunction "3V_55") (pintype "power_in"))
    )
    (net (code "105") (name "unconnected-(U1B-3V-Pad56)") (class "Default")
      (node (ref "U1") (pin "56") (pinfunction "3V_56") (pintype "power_in"))
    )
    (net (code "106") (name "unconnected-(U1B-5V-Pad53)") (class "Default")
      (node (ref "U1") (pin "53") (pinfunction "5V_53") (pintype "power_in"))
    )
    (net (code "107") (name "unconnected-(U1B-BOOT0-Pad71)") (class "Default")
      (node (ref "U1") (pin "71") (pinfunction "BOOT0_71") (pintype "input"))
    )
    (net (code "108") (name "unconnected-(U1B-GND-Pad51)") (class "Default")
      (node (ref "U1") (pin "51") (pinfunction "GND_51") (pintype "power_in"))
    )
    (net (code "109") (name "unconnected-(U1B-GND-Pad99)") (class "Default")
      (node (ref "U1") (pin "99") (pinfunction "GND_99") (pintype "power_in"))
    )
    (net (code "110") (name "unconnected-(U1B-GND-Pad100)") (class "Default")
      (node (ref "U1") (pin "100") (pinfunction "GND_100") (pintype "power_in"))
    )
    (net (code "111") (name "unconnected-(U1B-PA8-Pad93)") (class "Default")
      (node (ref "U1") (pin "93") (pinfunction "PA8_93") (pintype "bidirectional"))
    )
    (net (code "112") (name "unconnected-(U1B-PA9-Pad94)") (class "Default")
      (node (ref "U1") (pin "94") (pinfunction "PA9_94") (pintype "bidirectional"))
    )
    (net (code "113") (name "unconnected-(U1B-PA10-Pad91)") (class "Default")
      (node (ref "U1") (pin "91") (pinfunction "PA10_91") (pintype "bidirectional"))
    )
    (net (code "114") (name "unconnected-(U1B-PA13-Pad92)") (class "Default")
      (node (ref "U1") (pin "92") (pinfunction "PA13_92") (pintype "bidirectional"))
    )
    (net (code "115") (name "unconnected-(U1B-PA14-Pad89)") (class "Default")
      (node (ref "U1") (pin "89") (pinfunction "PA14_89") (pintype "bidirectional"))
    )
    (net (code "116") (name "unconnected-(U1B-PB3-Pad78)") (class "Default")
      (node (ref "U1") (pin "78") (pinfunction "PB3_78") (pintype "bidirectional"))
    )
    (net (code "117") (name "unconnected-(U1B-PB6-Pad73)") (class "Default")
      (node (ref "U1") (pin "73") (pinfunction "PB6_73") (pintype "bidirectional"))
    )
    (net (code "118") (name "unconnected-(U1B-PB7-Pad74)") (class "Default")
      (node (ref "U1") (pin "74") (pinfunction "PB7_74") (pintype "bidirectional"))
    )
    (net (code "119") (name "unconnected-(U1B-PB8-Pad69)") (class "Default")
      (node (ref "U1") (pin "69") (pinfunction "PB8_69") (pintype "bidirectional"))
    )
    (net (code "120") (name "unconnected-(U1B-PB9-Pad70)") (class "Default")
      (node (ref "U1") (pin "70") (pinfunction "PB9_70") (pintype "bidirectional"))
    )
    (net (code "121") (name "unconnected-(U1B-PC6-Pad97)") (class "Default")
      (node (ref "U1") (pin "97") (pinfunction "PC6_97") (pintype "bidirectional"))
    )
    (net (code "122") (name "unconnected-(U1B-PC7-Pad98)") (class "Default")
      (node (ref "U1") (pin "98") (pinfunction "PC7_98") (pintype "bidirectional"))
    )
    (net (code "123") (name "unconnected-(U1B-PC13-Pad62)") (class "Default")
      (node (ref "U1") (pin "62") (pinfunction "PC13_62") (pintype "bidirectional"))
    )
    (net (code "124") (name "unconnected-(U1B-PC14-Pad59)") (class "Default")
      (node (ref "U1") (pin "59") (pinfunction "PC14_59") (pintype "bidirectional"))
    )
    (net (code "125") (name "unconnected-(U1B-PC15-Pad60)") (class "Default")
      (node (ref "U1") (pin "60") (pinfunction "PC15_60") (pintype "bidirectional"))
    )
    (net (code "126") (name "unconnected-(U1B-PD4-Pad82)") (class "Default")
      (node (ref "U1") (pin "82") (pinfunction "PD4_82") (pintype "bidirectional"))
    )
    (net (code "127") (name "unconnected-(U1B-PD5-Pad79)") (class "Default")
      (node (ref "U1") (pin "79") (pinfunction "PD5_79") (pintype "bidirectional"))
    )
    (net (code "128") (name "unconnected-(U1B-PD6-Pad80)") (class "Default")
      (node (ref "U1") (pin "80") (pinfunction "PD6_80") (pintype "bidirectional"))
    )
    (net (code "129") (name "unconnected-(U1B-PD7-Pad77)") (class "Default")
      (node (ref "U1") (pin "77") (pinfunction "PD7_77") (pintype "bidirectional"))
    )
    (net (code "130") (name "unconnected-(U1B-PE0-Pad67)") (class "Default")
      (node (ref "U1") (pin "67") (pinfunction "PE0_67") (pintype "bidirectional"))
    )
    (net (code "131") (name "unconnected-(U1B-PE1-Pad68)") (class "Default")
      (node (ref "U1") (pin "68") (pinfunction "PE1_68") (pintype "bidirectional"))
    )
    (net (code "132") (name "unconnected-(U1B-PE2-Pad65)") (class "Default")
      (node (ref "U1") (pin "65") (pinfunction "PE2_65") (pintype "bidirectional"))
    )
    (net (code "133") (name "unconnected-(U1B-PH0-Pad57)") (class "Default")
      (node (ref "U1") (pin "57") (pinfunction "PH0_57") (pintype "bidirectional"))
    )
    (net (code "134") (name "unconnected-(U1B-PH1-Pad58)") (class "Default")
      (node (ref "U1") (pin "58") (pinfunction "PH1_58") (pintype "bidirectional"))
    )
    (net (code "135") (name "unconnected-(U1B-VDD-Pad72)") (class "Default")
      (node (ref "U1") (pin "72") (pinfunction "VDD_72") (pintype "power_in"))
    )
    (net (code "136") (name "unconnected-(U4-CD_SW-Pad10)") (class "Default")
      (node (ref "U4") (pin "10") (pinfunction "CD_SW_10") (pintype "passive"))
    )
    (net (code "137") (name "unconnected-(U4-DATA1-Pad8)") (class "Default")
      (node (ref "U4") (pin "8") (pinfunction "DATA1_8") (pintype "passive"))
    )
    (net (code "138") (name "unconnected-(U4-DATA2-Pad9)") (class "Default")
      (node (ref "U4") (pin "9") (pinfunction "DATA2_9") (pintype "passive"))
    )
    (net (code "139") (name "unconnected-(U4-SW_COMM-Pad12)") (class "Default")
      (node (ref "U4") (pin "12") (pinfunction "SW_COMM_12") (pintype "passive"))
    )
    (net (code "140") (name "unconnected-(U4-WP_SW-Pad11)") (class "Default")
      (node (ref "U4") (pin "11") (pinfunction "WP_SW_11") (pintype "passive"))
    )
    (net (code "141") (name "unconnected-(U4-mount_pad-Pad0)") (class "Default")
      (node (ref "U4") (pin "0") (pinfunction "mount_pad_0") (pintype "passive"))
    )
    (net (code "142") (name "unconnected-(U6-DRDY-Pad15)") (class "Default")
      (node (ref "U6") (pin "15") (pinfunction "DRDY_15") (pintype "passive"))
    )
    (net (code "143") (name "unconnected-(U6-T1-Pad23)") (class "Default")
      (node (ref "U6") (pin "23") (pinfunction "T1_23") (pintype "passive"))
    )
    (net (code "144") (name "unconnected-(U6-T2-Pad14)") (class "Default")
      (node (ref "U6") (pin "14") (pinfunction "T2_14") (pintype "passive"))
    )
    (net (code "145") (name "unconnected-(U7-BOOT-Pad12)") (class "Default")
      (node (ref "U7") (pin "12") (pinfunction "BOOT_12") (pintype "passive"))
    )
    (net (code "146") (name "unconnected-(U7-CTS-Pad10)") (class "Default")
      (node (ref "U7") (pin "10") (pinfunction "CTS_10") (pintype "passive"))
    )
    (net (code "147") (name "unconnected-(U7-GPIO1-Pad6)") (class "Default")
      (node (ref "U7") (pin "6") (pinfunction "GPIO1_6") (pintype "passive"))
    )
    (net (code "148") (name "unconnected-(U7-GPIO2-Pad5)") (class "Default")
      (node (ref "U7") (pin "5") (pinfunction "GPIO2_5") (pintype "passive"))
    )
    (net (code "149") (name "unconnected-(U7-GPIO3-Pad4)") (class "Default")
      (node (ref "U7") (pin "4") (pinfunction "GPIO3_4") (pintype "passive"))
    )
    (net (code "150") (name "unconnected-(U7-GPIO4-Pad3)") (class "Default")
      (node (ref "U7") (pin "3") (pinfunction "GPIO4_3") (pintype "passive"))
    )
    (net (code "151") (name "unconnected-(U7-RTS-Pad9)") (class "Default")
      (node (ref "U7") (pin "9") (pinfunction "RTS_9") (pintype "passive"))
    )
    (net (code "152") (name "unconnected-(U8-Pad5)") (class "Default")
      (node (ref "U8") (pin "5") (pintype "passive"))
    )
    (net (code "153") (name "unconnected-(U8-Pad6)") (class "Default")
      (node (ref "U8") (pin "6") (pintype "passive"))
    )
    (net (code "154") (name "unconnected-(U8-Pad11)") (class "Default")
      (node (ref "U8") (pin "11") (pintype "passive"))
    )
    (net (code "155") (name "unconnected-(U8-Pad12)") (class "Default")
      (node (ref "U8") (pin "12") (pintype "passive"))
    )
  )
)
